# TapuinoMini.net
KiCad netlist of a schematic drawn in EAGLE
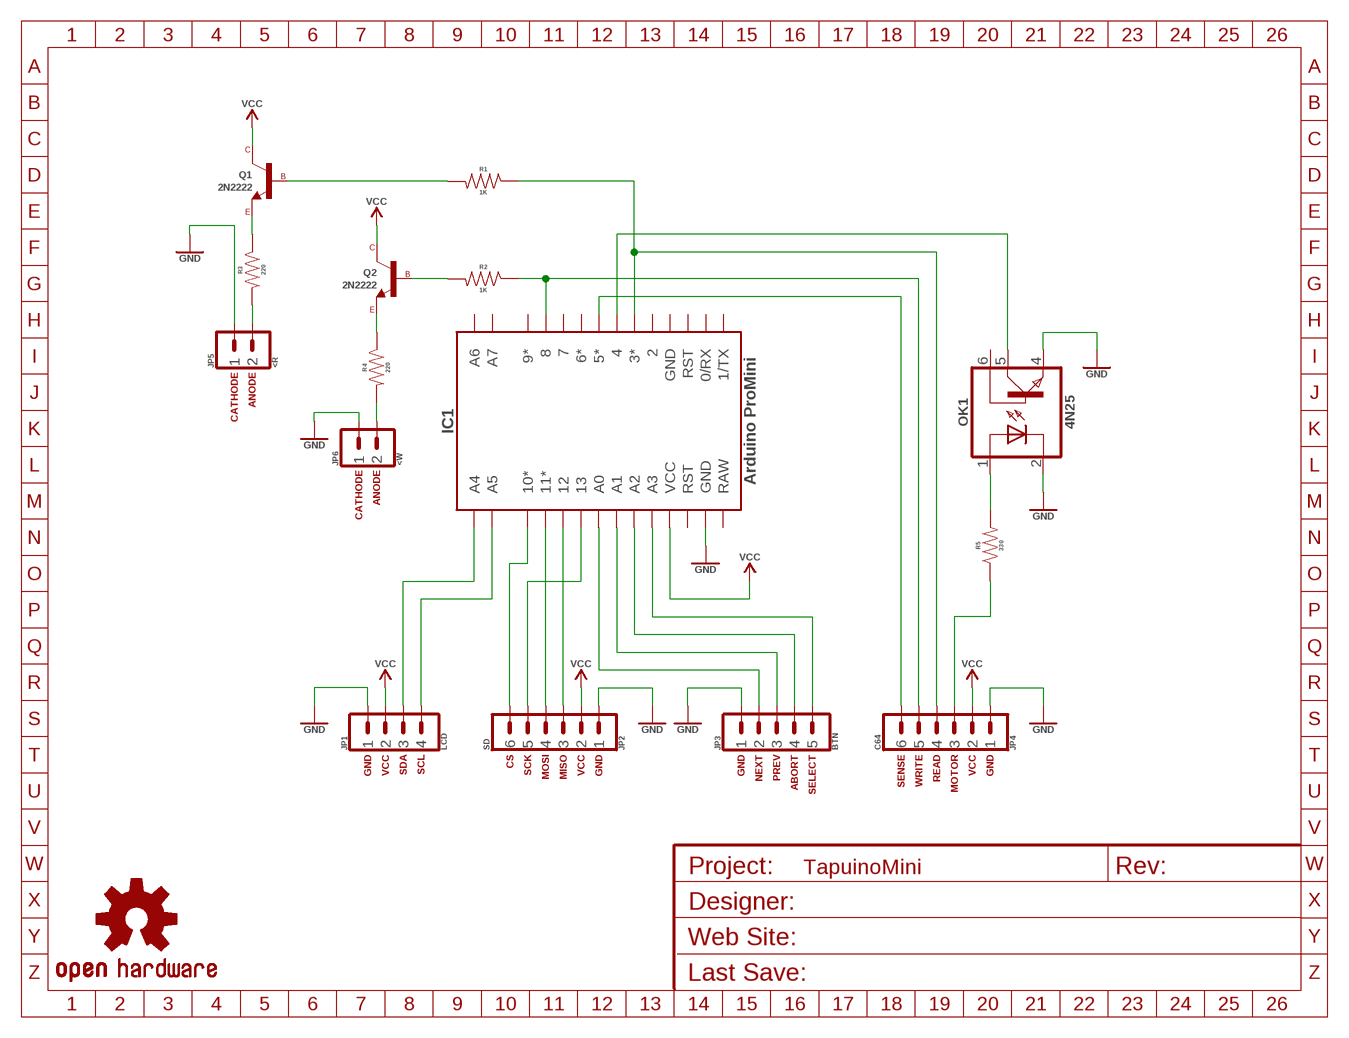
[diagram p0: schematic, sheet 1]

(export (version "E")
  (design (tool "Eeschema 10.0.6"))
  (components
    (comp (ref "IC1")
      (value "Arduino ProMini")
      (footprint "eagle-import:PROMINI_A")
      (libsource (lib "eagle-import") (part "PROMINI_A"))
    )
    (comp (ref "JP1")
      (value "LCD")
      (footprint "eagle-import:1X04_SQR")
      (libsource (lib "eagle-import") (part "1X04_SQR"))
    )
    (comp (ref "JP2")
      (value "SD")
      (footprint "eagle-import:1X06_SQR")
      (libsource (lib "eagle-import") (part "1X06_SQR"))
    )
    (comp (ref "JP3")
      (value "BTN")
      (footprint "eagle-import:1X05_SQR")
      (libsource (lib "eagle-import") (part "1X05_SQR"))
    )
    (comp (ref "JP4")
      (value "C64")
      (footprint "eagle-import:1X06_SQR")
      (libsource (lib "eagle-import") (part "1X06_SQR"))
    )
    (comp (ref "JP5")
      (value "<R")
      (footprint "eagle-import:1X02_SQR")
      (libsource (lib "eagle-import") (part "1X02_SQR"))
    )
    (comp (ref "JP6")
      (value "<W")
      (footprint "eagle-import:1X02_SQR")
      (libsource (lib "eagle-import") (part "1X02_SQR"))
    )
    (comp (ref "LOGO1")
      (value "OSHW_LOGO_SMALL")
      (footprint "eagle-import:OSHW_LOGO_SMALL")
      (libsource (lib "eagle-import") (part "OSHW_LOGO_SMALL"))
    )
    (comp (ref "OK1")
      (value "4N25")
      (footprint "eagle-import:DIP06")
      (libsource (lib "eagle-import") (part "OPTO_6PIN_4NXX"))
    )
    (comp (ref "Q1")
      (value "2N2222")
      (footprint "eagle-import:TO-92")
      (libsource (lib "eagle-import") (part "TRANSISTOR_NPN_EBC"))
    )
    (comp (ref "Q2")
      (value "2N2222")
      (footprint "eagle-import:TO-92")
      (libsource (lib "eagle-import") (part "TRANSISTOR_NPN_EBC"))
    )
    (comp (ref "R1")
      (value "1K")
      (footprint "eagle-import:RESISTOR_PTH_0.3")
      (libsource (lib "eagle-import") (part "RESISTOR_PTH_0.3"))
    )
    (comp (ref "R2")
      (value "1K")
      (footprint "eagle-import:RESISTOR_PTH_0.3")
      (libsource (lib "eagle-import") (part "RESISTOR_PTH_0.3"))
    )
    (comp (ref "R3")
      (value "220")
      (footprint "eagle-import:RESISTOR_PTH_0.3")
      (libsource (lib "eagle-import") (part "RESISTOR_PTH_0.3"))
    )
    (comp (ref "R4")
      (value "220")
      (footprint "eagle-import:RESISTOR_PTH_0.3")
      (libsource (lib "eagle-import") (part "RESISTOR_PTH_0.3"))
    )
    (comp (ref "R5")
      (value "330")
      (footprint "eagle-import:RESISTOR_PTH_0.3")
      (libsource (lib "eagle-import") (part "RESISTOR_PTH_0.3"))
    )
  )
  (nets
    (net (code "1") (name "GND") (class "Default")
      (node (ref "IC1") (pin "GND@1") (pinfunction "GND_GND@1") (pintype "bidirectional"))
      (node (ref "JP1") (pin "1") (pinfunction "1_1") (pintype "passive"))
      (node (ref "JP2") (pin "1") (pinfunction "1_1") (pintype "passive"))
      (node (ref "JP3") (pin "1") (pinfunction "1_1") (pintype "passive"))
      (node (ref "JP4") (pin "1") (pinfunction "1_1") (pintype "passive"))
      (node (ref "JP5") (pin "1") (pinfunction "1_1") (pintype "passive"))
      (node (ref "JP6") (pin "1") (pinfunction "1_1") (pintype "passive"))
      (node (ref "OK1") (pin "2") (pinfunction "CATHODE_2") (pintype "passive"))
      (node (ref "OK1") (pin "4") (pinfunction "EMITTER_4") (pintype "passive"))
    )
    (net (code "2") (name "Net-(IC1-Pad3*)") (class "Default")
      (node (ref "IC1") (pin "3*") (pinfunction "3*_3*") (pintype "bidirectional"))
      (node (ref "JP4") (pin "4") (pinfunction "4_4") (pintype "passive"))
      (node (ref "R1") (pin "1") (pinfunction "1_1") (pintype "passive"))
    )
    (net (code "3") (name "Net-(IC1-Pad5*)") (class "Default")
      (node (ref "IC1") (pin "5*") (pinfunction "5*_5*") (pintype "bidirectional"))
      (node (ref "JP4") (pin "6") (pinfunction "6_6") (pintype "passive"))
    )
    (net (code "4") (name "Net-(IC1-Pad8)") (class "Default")
      (node (ref "IC1") (pin "8") (pinfunction "8_8") (pintype "bidirectional"))
      (node (ref "JP4") (pin "5") (pinfunction "5_5") (pintype "passive"))
      (node (ref "R2") (pin "1") (pinfunction "1_1") (pintype "passive"))
    )
    (net (code "5") (name "Net-(IC1-Pad10*)") (class "Default")
      (node (ref "IC1") (pin "10*") (pinfunction "10*_10*") (pintype "bidirectional"))
      (node (ref "JP2") (pin "6") (pinfunction "6_6") (pintype "passive"))
    )
    (net (code "6") (name "Net-(IC1-Pad11*)") (class "Default")
      (node (ref "IC1") (pin "11*") (pinfunction "11*_11*") (pintype "bidirectional"))
      (node (ref "JP2") (pin "4") (pinfunction "4_4") (pintype "passive"))
    )
    (net (code "7") (name "Net-(IC1-Pad12)") (class "Default")
      (node (ref "IC1") (pin "12") (pinfunction "12_12") (pintype "bidirectional"))
      (node (ref "JP2") (pin "3") (pinfunction "3_3") (pintype "passive"))
    )
    (net (code "8") (name "Net-(IC1-Pad13)") (class "Default")
      (node (ref "IC1") (pin "13") (pinfunction "13_13") (pintype "bidirectional"))
      (node (ref "JP2") (pin "5") (pinfunction "5_5") (pintype "passive"))
    )
    (net (code "9") (name "Net-(IC1-PadA0)") (class "Default")
      (node (ref "IC1") (pin "A0") (pinfunction "A0_A0") (pintype "bidirectional"))
      (node (ref "JP3") (pin "2") (pinfunction "2_2") (pintype "passive"))
    )
    (net (code "10") (name "Net-(IC1-PadA1)") (class "Default")
      (node (ref "IC1") (pin "A1") (pinfunction "A1_A1") (pintype "bidirectional"))
      (node (ref "JP3") (pin "3") (pinfunction "3_3") (pintype "passive"))
    )
    (net (code "11") (name "Net-(IC1-PadA2)") (class "Default")
      (node (ref "IC1") (pin "A2") (pinfunction "A2_A2") (pintype "bidirectional"))
      (node (ref "JP3") (pin "4") (pinfunction "4_4") (pintype "passive"))
    )
    (net (code "12") (name "Net-(IC1-PadA3)") (class "Default")
      (node (ref "IC1") (pin "A3") (pinfunction "A3_A3") (pintype "bidirectional"))
      (node (ref "JP3") (pin "5") (pinfunction "5_5") (pintype "passive"))
    )
    (net (code "13") (name "Net-(IC1-PadA4)") (class "Default")
      (node (ref "IC1") (pin "A4") (pinfunction "A4_A4") (pintype "bidirectional"))
      (node (ref "JP1") (pin "3") (pinfunction "3_3") (pintype "passive"))
    )
    (net (code "14") (name "Net-(IC1-PadA5)") (class "Default")
      (node (ref "IC1") (pin "A5") (pinfunction "A5_A5") (pintype "bidirectional"))
      (node (ref "JP1") (pin "4") (pinfunction "4_4") (pintype "passive"))
    )
    (net (code "15") (name "Net-(JP4-Pad3)") (class "Default")
      (node (ref "JP4") (pin "3") (pinfunction "3_3") (pintype "passive"))
      (node (ref "R5") (pin "1") (pinfunction "1_1") (pintype "passive"))
    )
    (net (code "16") (name "Net-(JP5-Pad2)") (class "Default")
      (node (ref "JP5") (pin "2") (pinfunction "2_2") (pintype "passive"))
      (node (ref "R3") (pin "2") (pinfunction "2_2") (pintype "passive"))
    )
    (net (code "17") (name "Net-(JP6-Pad2)") (class "Default")
      (node (ref "JP6") (pin "2") (pinfunction "2_2") (pintype "passive"))
      (node (ref "R4") (pin "2") (pinfunction "2_2") (pintype "passive"))
    )
    (net (code "18") (name "Net-(OK1-ANODE)") (class "Default")
      (node (ref "OK1") (pin "1") (pinfunction "ANODE_1") (pintype "passive"))
      (node (ref "R5") (pin "2") (pinfunction "2_2") (pintype "passive"))
    )
    (net (code "19") (name "Net-(OK1-COLLECTOR)") (class "Default")
      (node (ref "IC1") (pin "4") (pinfunction "4_4") (pintype "bidirectional"))
      (node (ref "OK1") (pin "5") (pinfunction "COLLECTOR_5") (pintype "passive"))
    )
    (net (code "20") (name "Net-(Q1-BASE)") (class "Default")
      (node (ref "Q1") (pin "2") (pinfunction "BASE_2") (pintype "passive"))
      (node (ref "R1") (pin "2") (pinfunction "2_2") (pintype "passive"))
    )
    (net (code "21") (name "Net-(Q1-EMITTER)") (class "Default")
      (node (ref "Q1") (pin "1") (pinfunction "EMITTER_1") (pintype "passive"))
      (node (ref "R3") (pin "1") (pinfunction "1_1") (pintype "passive"))
    )
    (net (code "22") (name "Net-(Q2-BASE)") (class "Default")
      (node (ref "Q2") (pin "2") (pinfunction "BASE_2") (pintype "passive"))
      (node (ref "R2") (pin "2") (pinfunction "2_2") (pintype "passive"))
    )
    (net (code "23") (name "Net-(Q2-EMITTER)") (class "Default")
      (node (ref "Q2") (pin "1") (pinfunction "EMITTER_1") (pintype "passive"))
      (node (ref "R4") (pin "1") (pinfunction "1_1") (pintype "passive"))
    )
    (net (code "24") (name "VCC") (class "Default")
      (node (ref "IC1") (pin "VCC") (pinfunction "VCC_VCC") (pintype "bidirectional"))
      (node (ref "JP1") (pin "2") (pinfunction "2_2") (pintype "passive"))
      (node (ref "JP2") (pin "2") (pinfunction "2_2") (pintype "passive"))
      (node (ref "JP4") (pin "2") (pinfunction "2_2") (pintype "passive"))
      (node (ref "Q1") (pin "3") (pinfunction "COLLECTOR_3") (pintype "passive"))
      (node (ref "Q2") (pin "3") (pinfunction "COLLECTOR_3") (pintype "passive"))
    )
    (net (code "25") (name "unconnected-(IC1-GND-PadGND@2)") (class "Default")
      (node (ref "IC1") (pin "GND@2") (pinfunction "GND_GND@2") (pintype "bidirectional"))
    )
    (net (code "26") (name "unconnected-(IC1-Pad0{slash}RX)") (class "Default")
      (node (ref "IC1") (pin "0/RX") (pinfunction "0/RX_0/RX") (pintype "bidirectional"))
    )
    (net (code "27") (name "unconnected-(IC1-Pad1{slash}TX)") (class "Default")
      (node (ref "IC1") (pin "1/TX") (pinfunction "1/TX_1/TX") (pintype "bidirectional"))
    )
    (net (code "28") (name "unconnected-(IC1-Pad2)") (class "Default")
      (node (ref "IC1") (pin "2") (pinfunction "2_2") (pintype "bidirectional"))
    )
    (net (code "29") (name "unconnected-(IC1-Pad6*)") (class "Default")
      (node (ref "IC1") (pin "6*") (pinfunction "6*_6*") (pintype "bidirectional"))
    )
    (net (code "30") (name "unconnected-(IC1-Pad7)") (class "Default")
      (node (ref "IC1") (pin "7") (pinfunction "7_7") (pintype "bidirectional"))
    )
    (net (code "31") (name "unconnected-(IC1-Pad9*)") (class "Default")
      (node (ref "IC1") (pin "9*") (pinfunction "9*_9*") (pintype "bidirectional"))
    )
    (net (code "32") (name "unconnected-(IC1-PadA6)") (class "Default")
      (node (ref "IC1") (pin "A6") (pinfunction "A6_A6") (pintype "bidirectional"))
    )
    (net (code "33") (name "unconnected-(IC1-PadA7)") (class "Default")
      (node (ref "IC1") (pin "A7") (pinfunction "A7_A7") (pintype "bidirectional"))
    )
    (net (code "34") (name "unconnected-(IC1-PadRAW)") (class "Default")
      (node (ref "IC1") (pin "RAW") (pinfunction "RAW_RAW") (pintype "bidirectional"))
    )
    (net (code "35") (name "unconnected-(IC1-RST-PadRST@1)") (class "Default")
      (node (ref "IC1") (pin "RST@1") (pinfunction "RST_RST@1") (pintype "bidirectional"))
    )
    (net (code "36") (name "unconnected-(IC1-RST-PadRST@2)") (class "Default")
      (node (ref "IC1") (pin "RST@2") (pinfunction "RST_RST@2") (pintype "bidirectional"))
    )
    (net (code "37") (name "unconnected-(OK1-BASE-Pad6)") (class "Default")
      (node (ref "OK1") (pin "6") (pinfunction "BASE_6") (pintype "passive"))
    )
  )
)
